# c8t6.net
KiCad netlist of a schematic drawn in Altium Designer
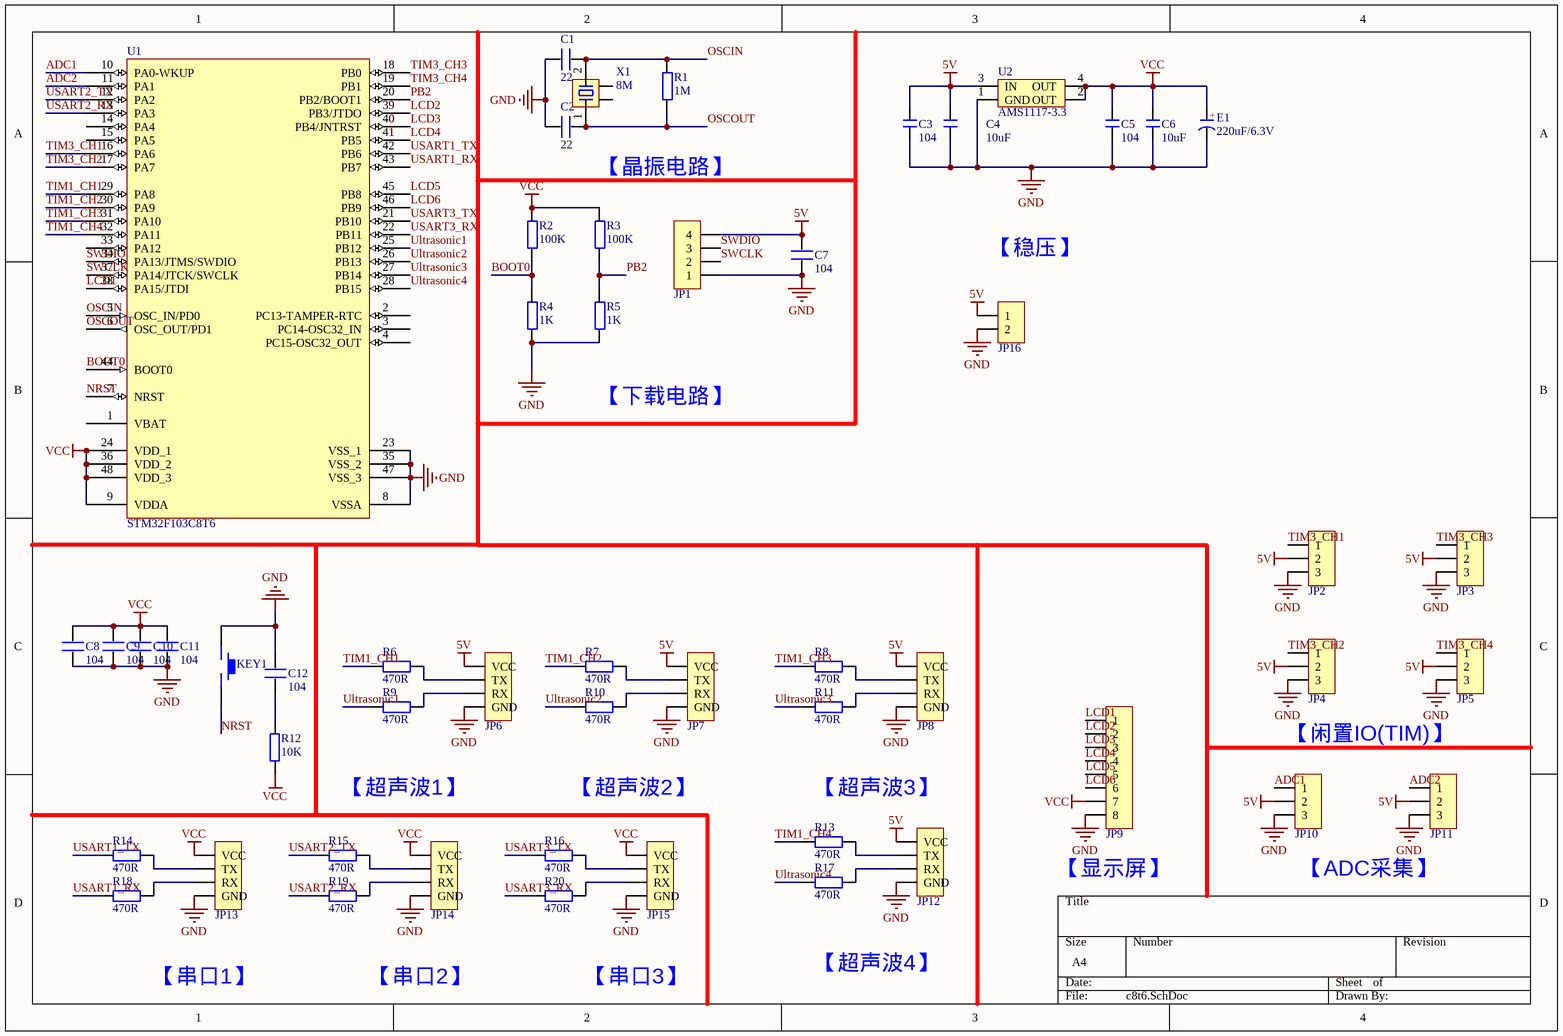
[diagram p0: c8t6.SchDoc]

(export (version "E")
  (design (tool "Eeschema 10.0.6"))
  (components
    (comp (ref "C1") (value "22") (footprint "C 0603") (libsource (lib "CORE") (part "C")))
    (comp (ref "C2") (value "22") (footprint "C 0603") (libsource (lib "CORE") (part "C")))
    (comp (ref "C3")
      (value "104")
      (footprint "C 0603")
      (description "无极性贴片电容")
      (fields (field (name "版权归属") "源创客"))
      (libsource (lib "daplink") (part "C"))
    )
    (comp (ref "C4")
      (value "10uF")
      (footprint "C 0805")
      (description "无极性贴片电容")
      (fields (field (name "版权归属") "源创客"))
      (libsource (lib "daplink") (part "C"))
    )
    (comp (ref "C5")
      (value "104")
      (footprint "C 0603")
      (description "无极性贴片电容")
      (fields (field (name "版权归属") "源创客"))
      (libsource (lib "daplink") (part "C"))
    )
    (comp (ref "C6")
      (value "10uF")
      (footprint "C 0805")
      (description "无极性贴片电容")
      (fields (field (name "版权归属") "源创客"))
      (libsource (lib "daplink") (part "C"))
    )
    (comp (ref "C7") (value "104") (footprint "C 0603") (libsource (lib "CORE") (part "C")))
    (comp (ref "C8") (value "104") (footprint "C 0603") (libsource (lib "CORE") (part "C")))
    (comp (ref "C9") (value "104") (footprint "C 0603") (libsource (lib "CORE") (part "C")))
    (comp (ref "C10") (value "104") (footprint "C 0603") (libsource (lib "CORE") (part "C")))
    (comp (ref "C11") (value "104") (footprint "C 0603") (libsource (lib "CORE") (part "C")))
    (comp (ref "C12") (value "104") (footprint "C 0603") (libsource (lib "CORE") (part "C")))
    (comp (ref "E1")
      (value "220uF/6.3V")
      (footprint "CD C(6032)")
      (description "贴片钽电容")
      (fields (field (name "版权归属") "源创客"))
      (libsource (lib "电阻-电容-电感") (part "C-CD"))
    )
    (comp (ref "JP1")
      (value "HDR-1X4")
      (footprint "XH2.54-4P")
      (description "4P接插件")
      (fields (field (name "版权归属") "源创客"))
      (libsource (lib "") (part "Header 4_1"))
    )
    (comp (ref "JP2")
      (value "HDR-1X3")
      (footprint "HDR-1X3")
      (description "3P接插件")
      (fields (field (name "版权归属") "源创客"))
      (libsource (lib "接插件") (part "Header 3"))
    )
    (comp (ref "JP3")
      (value "HDR-1X3")
      (footprint "HDR-1X3")
      (description "3P接插件")
      (fields (field (name "版权归属") "源创客"))
      (libsource (lib "接插件") (part "Header 3"))
    )
    (comp (ref "JP4")
      (value "HDR-1X3")
      (footprint "HDR-1X3")
      (description "3P接插件")
      (fields (field (name "版权归属") "源创客"))
      (libsource (lib "接插件") (part "Header 3"))
    )
    (comp (ref "JP5")
      (value "HDR-1X3")
      (footprint "HDR-1X3")
      (description "3P接插件")
      (fields (field (name "版权归属") "源创客"))
      (libsource (lib "接插件") (part "Header 3"))
    )
    (comp (ref "JP6")
      (value "HDR-1X4")
      (footprint "XH2.54-4P")
      (description "4P接插件")
      (fields (field (name "版权归属") "源创客"))
      (libsource (lib "接插件") (part "Header 4"))
    )
    (comp (ref "JP7")
      (value "HDR-1X4")
      (footprint "XH2.54-4P")
      (description "4P接插件")
      (fields (field (name "版权归属") "源创客"))
      (libsource (lib "接插件") (part "Header 4"))
    )
    (comp (ref "JP8")
      (value "HDR-1X4")
      (footprint "XH2.54-4P")
      (description "4P接插件")
      (fields (field (name "版权归属") "源创客"))
      (libsource (lib "接插件") (part "Header 4"))
    )
    (comp (ref "JP9")
      (value "HDR-1X8")
      (footprint "HDR-1X8")
      (description "8P接插件")
      (fields (field (name "版权归属") "源创客"))
      (libsource (lib "接插件") (part "Header 8"))
    )
    (comp (ref "JP10")
      (value "HDR-1X3")
      (footprint "HDR-1X3")
      (description "3P接插件")
      (fields (field (name "版权归属") "源创客"))
      (libsource (lib "接插件") (part "Header 3"))
    )
    (comp (ref "JP11")
      (value "HDR-1X3")
      (footprint "HDR-1X3")
      (description "3P接插件")
      (fields (field (name "版权归属") "源创客"))
      (libsource (lib "接插件") (part "Header 3"))
    )
    (comp (ref "JP12")
      (value "HDR-1X4")
      (footprint "XH2.54-4P")
      (description "4P接插件")
      (fields (field (name "版权归属") "源创客"))
      (libsource (lib "接插件") (part "Header 4"))
    )
    (comp (ref "JP13")
      (value "HDR-1X4")
      (footprint "XH2.54-4P")
      (description "4P接插件")
      (fields (field (name "版权归属") "源创客"))
      (libsource (lib "接插件") (part "Header 4"))
    )
    (comp (ref "JP14")
      (value "HDR-1X4")
      (footprint "XH2.54-4P")
      (description "4P接插件")
      (fields (field (name "版权归属") "源创客"))
      (libsource (lib "接插件") (part "Header 4"))
    )
    (comp (ref "JP15")
      (value "HDR-1X4")
      (footprint "XH2.54-4P")
      (description "4P接插件")
      (fields (field (name "版权归属") "源创客"))
      (libsource (lib "接插件") (part "Header 4"))
    )
    (comp (ref "JP16")
      (value "HDR-1X2")
      (footprint "XT60")
      (description "2P接插件")
      (fields (field (name "版权归属") "源创客"))
      (libsource (lib "接插件") (part "Header 2"))
    )
    (comp (ref "KEY1") (value "KEY_M") (footprint "TSW DIP-3*6*4.3") (libsource (lib "CORE") (part "KEY_M")))
    (comp (ref "R1") (value "1M") (footprint "R 0603") (libsource (lib "CORE") (part "R")))
    (comp (ref "R2") (value "100K") (footprint "R 0603") (libsource (lib "CORE") (part "R")))
    (comp (ref "R3") (value "100K") (footprint "R 0603") (libsource (lib "CORE") (part "R")))
    (comp (ref "R4") (value "1K") (footprint "R 0603") (libsource (lib "CORE") (part "R")))
    (comp (ref "R5") (value "1K") (footprint "R 0603") (libsource (lib "CORE") (part "R")))
    (comp (ref "R6")
      (value "470R")
      (footprint "R 0603")
      (description "贴片电阻")
      (fields (field (name "版权归属") "源创客"))
      (libsource (lib "电阻-电容-电感") (part "R"))
    )
    (comp (ref "R7")
      (value "470R")
      (footprint "R 0603")
      (description "贴片电阻")
      (fields (field (name "版权归属") "源创客"))
      (libsource (lib "电阻-电容-电感") (part "R"))
    )
    (comp (ref "R8")
      (value "470R")
      (footprint "R 0603")
      (description "贴片电阻")
      (fields (field (name "版权归属") "源创客"))
      (libsource (lib "电阻-电容-电感") (part "R"))
    )
    (comp (ref "R9")
      (value "470R")
      (footprint "R 0603")
      (description "贴片电阻")
      (fields (field (name "版权归属") "源创客"))
      (libsource (lib "电阻-电容-电感") (part "R"))
    )
    (comp (ref "R10")
      (value "470R")
      (footprint "R 0603")
      (description "贴片电阻")
      (fields (field (name "版权归属") "源创客"))
      (libsource (lib "电阻-电容-电感") (part "R"))
    )
    (comp (ref "R11")
      (value "470R")
      (footprint "R 0603")
      (description "贴片电阻")
      (fields (field (name "版权归属") "源创客"))
      (libsource (lib "电阻-电容-电感") (part "R"))
    )
    (comp (ref "R12") (value "10K") (footprint "R 0603") (libsource (lib "MPU6050") (part "R")))
    (comp (ref "R13")
      (value "470R")
      (footprint "R 0603")
      (description "贴片电阻")
      (fields (field (name "版权归属") "源创客"))
      (libsource (lib "电阻-电容-电感") (part "R"))
    )
    (comp (ref "R14")
      (value "470R")
      (footprint "R 0603")
      (description "贴片电阻")
      (fields (field (name "版权归属") "源创客"))
      (libsource (lib "电阻-电容-电感") (part "R"))
    )
    (comp (ref "R15")
      (value "470R")
      (footprint "R 0603")
      (description "贴片电阻")
      (fields (field (name "版权归属") "源创客"))
      (libsource (lib "电阻-电容-电感") (part "R"))
    )
    (comp (ref "R16")
      (value "470R")
      (footprint "R 0603")
      (description "贴片电阻")
      (fields (field (name "版权归属") "源创客"))
      (libsource (lib "电阻-电容-电感") (part "R"))
    )
    (comp (ref "R17")
      (value "470R")
      (footprint "R 0603")
      (description "贴片电阻")
      (fields (field (name "版权归属") "源创客"))
      (libsource (lib "电阻-电容-电感") (part "R"))
    )
    (comp (ref "R18")
      (value "470R")
      (footprint "R 0603")
      (description "贴片电阻")
      (fields (field (name "版权归属") "源创客"))
      (libsource (lib "电阻-电容-电感") (part "R"))
    )
    (comp (ref "R19")
      (value "470R")
      (footprint "R 0603")
      (description "贴片电阻")
      (fields (field (name "版权归属") "源创客"))
      (libsource (lib "电阻-电容-电感") (part "R"))
    )
    (comp (ref "R20")
      (value "470R")
      (footprint "R 0603")
      (description "贴片电阻")
      (fields (field (name "版权归属") "源创客"))
      (libsource (lib "电阻-电容-电感") (part "R"))
    )
    (comp (ref "U1")
      (value "STM32F103C8T6")
      (footprint "LQFP48 7X7_M")
      (description "Flaah:64/RAM:20/IO:36")
      (fields (field (name "版权归属") "源创客"))
      (libsource (lib "STM32系列单片机") (part "STM32F103C8T6"))
    )
    (comp (ref "U2") (value "AMS1117-3.3") (footprint "SOT223_L") (libsource (lib "GWH") (part "AMS1117")))
    (comp (ref "X1")
      (value "8M")
      (footprint "XTAL-49S DIP")
      (description "4脚晶振")
      (fields (field (name "版权归属") "源创客"))
      (libsource (lib "保险丝-晶振") (part "XTAL-4"))
    )
  )
  (nets
    (net (code "1") (name "/ADC1") (class "Default")
      (node (ref "JP10") (pin "1") (pinfunction "1_1") (pintype "passive"))
      (node (ref "U1") (pin "10") (pinfunction "PA0-WKUP_10") (pintype "bidirectional"))
    )
    (net (code "2") (name "/ADC2") (class "Default")
      (node (ref "JP11") (pin "1") (pinfunction "1_1") (pintype "passive"))
      (node (ref "U1") (pin "11") (pinfunction "PA1_11") (pintype "bidirectional"))
    )
    (net (code "3") (name "/BOOT0") (class "Default")
      (node (ref "R2") (pin "1") (pintype "passive"))
      (node (ref "R4") (pin "2") (pintype "passive"))
      (node (ref "U1") (pin "44") (pinfunction "BOOT0_44") (pintype "input"))
    )
    (net (code "4") (name "/LCD1") (class "Default")
      (node (ref "JP9") (pin "1") (pinfunction "1_1") (pintype "passive"))
      (node (ref "U1") (pin "38") (pinfunction "PA15/JTDI_38") (pintype "bidirectional"))
    )
    (net (code "5") (name "/LCD2") (class "Default")
      (node (ref "JP9") (pin "2") (pinfunction "2_2") (pintype "passive"))
      (node (ref "U1") (pin "39") (pinfunction "PB3/JTDO_39") (pintype "bidirectional"))
    )
    (net (code "6") (name "/LCD3") (class "Default")
      (node (ref "JP9") (pin "3") (pinfunction "3_3") (pintype "passive"))
      (node (ref "U1") (pin "40") (pinfunction "PB4/JNTRST_40") (pintype "bidirectional"))
    )
    (net (code "7") (name "/LCD4") (class "Default")
      (node (ref "JP9") (pin "4") (pinfunction "4_4") (pintype "passive"))
      (node (ref "U1") (pin "41") (pinfunction "PB5_41") (pintype "bidirectional"))
    )
    (net (code "8") (name "/LCD5") (class "Default")
      (node (ref "JP9") (pin "5") (pinfunction "5_5") (pintype "passive"))
      (node (ref "U1") (pin "45") (pinfunction "PB8_45") (pintype "bidirectional"))
    )
    (net (code "9") (name "/LCD6") (class "Default")
      (node (ref "JP9") (pin "6") (pinfunction "6_6") (pintype "passive"))
      (node (ref "U1") (pin "46") (pinfunction "PB9_46") (pintype "bidirectional"))
    )
    (net (code "10") (name "/NRST") (class "Default")
      (node (ref "KEY1") (pin "2") (pinfunction "2_2") (pintype "passive"))
      (node (ref "U1") (pin "7") (pinfunction "NRST_7") (pintype "bidirectional"))
    )
    (net (code "11") (name "/OSCIN") (class "Default")
      (node (ref "C1") (pin "1") (pintype "passive"))
      (node (ref "R1") (pin "2") (pintype "passive"))
      (node (ref "U1") (pin "5") (pinfunction "OSC_IN/PD0_5") (pintype "input"))
      (node (ref "X1") (pin "2") (pinfunction "3_2") (pintype "passive"))
    )
    (net (code "12") (name "/OSCOUT") (class "Default")
      (node (ref "C2") (pin "1") (pintype "passive"))
      (node (ref "R1") (pin "1") (pintype "passive"))
      (node (ref "U1") (pin "6") (pinfunction "OSC_OUT/PD1_6") (pintype "output"))
      (node (ref "X1") (pin "1") (pinfunction "1_1") (pintype "passive"))
    )
    (net (code "13") (name "/PB2") (class "Default")
      (node (ref "R3") (pin "1") (pintype "passive"))
      (node (ref "R5") (pin "2") (pintype "passive"))
      (node (ref "U1") (pin "20") (pinfunction "PB2/BOOT1_20") (pintype "bidirectional"))
    )
    (net (code "14") (name "/SWCLK") (class "Default")
      (node (ref "JP1") (pin "2") (pinfunction "2_2") (pintype "passive"))
      (node (ref "U1") (pin "37") (pinfunction "PA14/JTCK/SWCLK_37") (pintype "bidirectional"))
    )
    (net (code "15") (name "/SWDIO") (class "Default")
      (node (ref "JP1") (pin "3") (pinfunction "3_3") (pintype "passive"))
      (node (ref "U1") (pin "34") (pinfunction "PA13/JTMS/SWDIO_34") (pintype "bidirectional"))
    )
    (net (code "16") (name "/TIM1_CH1") (class "Default")
      (node (ref "R6") (pin "1") (pinfunction "1_1") (pintype "passive"))
      (node (ref "U1") (pin "29") (pinfunction "PA8_29") (pintype "bidirectional"))
    )
    (net (code "17") (name "/TIM1_CH2") (class "Default")
      (node (ref "R7") (pin "1") (pinfunction "1_1") (pintype "passive"))
      (node (ref "U1") (pin "30") (pinfunction "PA9_30") (pintype "bidirectional"))
    )
    (net (code "18") (name "/TIM1_CH3") (class "Default")
      (node (ref "R8") (pin "1") (pinfunction "1_1") (pintype "passive"))
      (node (ref "U1") (pin "31") (pinfunction "PA10_31") (pintype "bidirectional"))
    )
    (net (code "19") (name "/TIM1_CH4") (class "Default")
      (node (ref "R13") (pin "1") (pinfunction "1_1") (pintype "passive"))
      (node (ref "U1") (pin "32") (pinfunction "PA11_32") (pintype "bidirectional"))
    )
    (net (code "20") (name "/TIM3_CH1") (class "Default")
      (node (ref "JP2") (pin "1") (pinfunction "1_1") (pintype "passive"))
      (node (ref "U1") (pin "16") (pinfunction "PA6_16") (pintype "bidirectional"))
    )
    (net (code "21") (name "/TIM3_CH2") (class "Default")
      (node (ref "JP4") (pin "1") (pinfunction "1_1") (pintype "passive"))
      (node (ref "U1") (pin "17") (pinfunction "PA7_17") (pintype "bidirectional"))
    )
    (net (code "22") (name "/TIM3_CH3") (class "Default")
      (node (ref "JP3") (pin "1") (pinfunction "1_1") (pintype "passive"))
      (node (ref "U1") (pin "18") (pinfunction "PB0_18") (pintype "bidirectional"))
    )
    (net (code "23") (name "/TIM3_CH4") (class "Default")
      (node (ref "JP5") (pin "1") (pinfunction "1_1") (pintype "passive"))
      (node (ref "U1") (pin "19") (pinfunction "PB1_19") (pintype "bidirectional"))
    )
    (net (code "24") (name "/USART1_RX") (class "Default")
      (node (ref "R18") (pin "1") (pinfunction "1_1") (pintype "passive"))
      (node (ref "U1") (pin "43") (pinfunction "PB7_43") (pintype "bidirectional"))
    )
    (net (code "25") (name "/USART1_TX") (class "Default")
      (node (ref "R14") (pin "1") (pinfunction "1_1") (pintype "passive"))
      (node (ref "U1") (pin "42") (pinfunction "PB6_42") (pintype "bidirectional"))
    )
    (net (code "26") (name "/USART2_RX") (class "Default")
      (node (ref "R19") (pin "1") (pinfunction "1_1") (pintype "passive"))
      (node (ref "U1") (pin "13") (pinfunction "PA3_13") (pintype "bidirectional"))
    )
    (net (code "27") (name "/USART2_TX") (class "Default")
      (node (ref "R15") (pin "1") (pinfunction "1_1") (pintype "passive"))
      (node (ref "U1") (pin "12") (pinfunction "PA2_12") (pintype "bidirectional"))
    )
    (net (code "28") (name "/USART3_RX") (class "Default")
      (node (ref "R20") (pin "1") (pinfunction "1_1") (pintype "passive"))
      (node (ref "U1") (pin "22") (pinfunction "PB11_22") (pintype "bidirectional"))
    )
    (net (code "29") (name "/USART3_TX") (class "Default")
      (node (ref "R16") (pin "1") (pinfunction "1_1") (pintype "passive"))
      (node (ref "U1") (pin "21") (pinfunction "PB10_21") (pintype "bidirectional"))
    )
    (net (code "30") (name "/Ultrasonic1") (class "Default")
      (node (ref "R9") (pin "1") (pinfunction "1_1") (pintype "passive"))
      (node (ref "U1") (pin "25") (pinfunction "PB12_25") (pintype "bidirectional"))
    )
    (net (code "31") (name "/Ultrasonic2") (class "Default")
      (node (ref "R10") (pin "1") (pinfunction "1_1") (pintype "passive"))
      (node (ref "U1") (pin "26") (pinfunction "PB13_26") (pintype "bidirectional"))
    )
    (net (code "32") (name "/Ultrasonic3") (class "Default")
      (node (ref "R11") (pin "1") (pinfunction "1_1") (pintype "passive"))
      (node (ref "U1") (pin "27") (pinfunction "PB14_27") (pintype "bidirectional"))
    )
    (net (code "33") (name "/Ultrasonic4") (class "Default")
      (node (ref "R17") (pin "1") (pinfunction "1_1") (pintype "passive"))
      (node (ref "U1") (pin "28") (pinfunction "PB15_28") (pintype "bidirectional"))
    )
    (net (code "34") (name "5V") (class "Default")
      (node (ref "C3") (pin "2") (pinfunction "2_2") (pintype "passive"))
      (node (ref "C4") (pin "2") (pinfunction "2_2") (pintype "passive"))
      (node (ref "C7") (pin "1") (pintype "passive"))
      (node (ref "JP1") (pin "4") (pinfunction "4_4") (pintype "passive"))
      (node (ref "JP10") (pin "2") (pinfunction "2_2") (pintype "passive"))
      (node (ref "JP11") (pin "2") (pinfunction "2_2") (pintype "passive"))
      (node (ref "JP12") (pin "1") (pinfunction "VCC_1") (pintype "passive"))
      (node (ref "JP16") (pin "1") (pinfunction "1_1") (pintype "passive"))
      (node (ref "JP2") (pin "2") (pinfunction "2_2") (pintype "passive"))
      (node (ref "JP3") (pin "2") (pinfunction "2_2") (pintype "passive"))
      (node (ref "JP4") (pin "2") (pinfunction "2_2") (pintype "passive"))
      (node (ref "JP5") (pin "2") (pinfunction "2_2") (pintype "passive"))
      (node (ref "JP6") (pin "1") (pinfunction "VCC_1") (pintype "passive"))
      (node (ref "JP7") (pin "1") (pinfunction "VCC_1") (pintype "passive"))
      (node (ref "JP8") (pin "1") (pinfunction "VCC_1") (pintype "passive"))
      (node (ref "U2") (pin "3") (pinfunction "IN_3") (pintype "passive"))
    )
    (net (code "35") (name "GND") (class "Default")
      (node (ref "C1") (pin "2") (pintype "passive"))
      (node (ref "C10") (pin "2") (pintype "passive"))
      (node (ref "C11") (pin "2") (pintype "passive"))
      (node (ref "C12") (pin "2") (pintype "passive"))
      (node (ref "C2") (pin "2") (pintype "passive"))
      (node (ref "C3") (pin "1") (pinfunction "1_1") (pintype "passive"))
      (node (ref "C4") (pin "1") (pinfunction "1_1") (pintype "passive"))
      (node (ref "C5") (pin "1") (pinfunction "1_1") (pintype "passive"))
      (node (ref "C6") (pin "1") (pinfunction "1_1") (pintype "passive"))
      (node (ref "C7") (pin "2") (pintype "passive"))
      (node (ref "C8") (pin "2") (pintype "passive"))
      (node (ref "C9") (pin "2") (pintype "passive"))
      (node (ref "E1") (pin "2") (pinfunction "K_2") (pintype "passive"))
      (node (ref "JP1") (pin "1") (pinfunction "1_1") (pintype "passive"))
      (node (ref "JP10") (pin "3") (pinfunction "3_3") (pintype "passive"))
      (node (ref "JP11") (pin "3") (pinfunction "3_3") (pintype "passive"))
      (node (ref "JP12") (pin "4") (pinfunction "GND_4") (pintype "passive"))
      (node (ref "JP13") (pin "4") (pinfunction "GND_4") (pintype "passive"))
      (node (ref "JP14") (pin "4") (pinfunction "GND_4") (pintype "passive"))
      (node (ref "JP15") (pin "4") (pinfunction "GND_4") (pintype "passive"))
      (node (ref "JP16") (pin "2") (pinfunction "2_2") (pintype "passive"))
      (node (ref "JP2") (pin "3") (pinfunction "3_3") (pintype "passive"))
      (node (ref "JP3") (pin "3") (pinfunction "3_3") (pintype "passive"))
      (node (ref "JP4") (pin "3") (pinfunction "3_3") (pintype "passive"))
      (node (ref "JP5") (pin "3") (pinfunction "3_3") (pintype "passive"))
      (node (ref "JP6") (pin "4") (pinfunction "GND_4") (pintype "passive"))
      (node (ref "JP7") (pin "4") (pinfunction "GND_4") (pintype "passive"))
      (node (ref "JP8") (pin "4") (pinfunction "GND_4") (pintype "passive"))
      (node (ref "JP9") (pin "8") (pinfunction "8_8") (pintype "passive"))
      (node (ref "KEY1") (pin "1") (pinfunction "1_1") (pintype "passive"))
      (node (ref "R4") (pin "1") (pintype "passive"))
      (node (ref "R5") (pin "1") (pintype "passive"))
      (node (ref "U1") (pin "23") (pinfunction "VSS_1_23") (pintype "power_in"))
      (node (ref "U1") (pin "35") (pinfunction "VSS_2_35") (pintype "power_in"))
      (node (ref "U1") (pin "47") (pinfunction "VSS_3_47") (pintype "power_in"))
      (node (ref "U1") (pin "8") (pinfunction "VSSA_8") (pintype "power_in"))
      (node (ref "U2") (pin "1") (pinfunction "GND_1") (pintype "passive"))
    )
    (net (code "36") (name "Net-(C12-Pad1)") (class "Default")
      (node (ref "C12") (pin "1") (pintype "passive"))
      (node (ref "R12") (pin "1") (pintype "passive"))
    )
    (net (code "37") (name "Net-(JP6-RX)") (class "Default")
      (node (ref "JP6") (pin "3") (pinfunction "RX_3") (pintype "passive"))
      (node (ref "R9") (pin "2") (pinfunction "2_2") (pintype "passive"))
    )
    (net (code "38") (name "Net-(JP6-TX)") (class "Default")
      (node (ref "JP6") (pin "2") (pinfunction "TX_2") (pintype "passive"))
      (node (ref "R6") (pin "2") (pinfunction "2_2") (pintype "passive"))
    )
    (net (code "39") (name "Net-(JP7-RX)") (class "Default")
      (node (ref "JP7") (pin "3") (pinfunction "RX_3") (pintype "passive"))
      (node (ref "R10") (pin "2") (pinfunction "2_2") (pintype "passive"))
    )
    (net (code "40") (name "Net-(JP7-TX)") (class "Default")
      (node (ref "JP7") (pin "2") (pinfunction "TX_2") (pintype "passive"))
      (node (ref "R7") (pin "2") (pinfunction "2_2") (pintype "passive"))
    )
    (net (code "41") (name "Net-(JP8-RX)") (class "Default")
      (node (ref "JP8") (pin "3") (pinfunction "RX_3") (pintype "passive"))
      (node (ref "R11") (pin "2") (pinfunction "2_2") (pintype "passive"))
    )
    (net (code "42") (name "Net-(JP8-TX)") (class "Default")
      (node (ref "JP8") (pin "2") (pinfunction "TX_2") (pintype "passive"))
      (node (ref "R8") (pin "2") (pinfunction "2_2") (pintype "passive"))
    )
    (net (code "43") (name "Net-(JP12-RX)") (class "Default")
      (node (ref "JP12") (pin "3") (pinfunction "RX_3") (pintype "passive"))
      (node (ref "R17") (pin "2") (pinfunction "2_2") (pintype "passive"))
    )
    (net (code "44") (name "Net-(JP12-TX)") (class "Default")
      (node (ref "JP12") (pin "2") (pinfunction "TX_2") (pintype "passive"))
      (node (ref "R13") (pin "2") (pinfunction "2_2") (pintype "passive"))
    )
    (net (code "45") (name "Net-(JP13-RX)") (class "Default")
      (node (ref "JP13") (pin "3") (pinfunction "RX_3") (pintype "passive"))
      (node (ref "R18") (pin "2") (pinfunction "2_2") (pintype "passive"))
    )
    (net (code "46") (name "Net-(JP13-TX)") (class "Default")
      (node (ref "JP13") (pin "2") (pinfunction "TX_2") (pintype "passive"))
      (node (ref "R14") (pin "2") (pinfunction "2_2") (pintype "passive"))
    )
    (net (code "47") (name "Net-(JP14-RX)") (class "Default")
      (node (ref "JP14") (pin "3") (pinfunction "RX_3") (pintype "passive"))
      (node (ref "R19") (pin "2") (pinfunction "2_2") (pintype "passive"))
    )
    (net (code "48") (name "Net-(JP14-TX)") (class "Default")
      (node (ref "JP14") (pin "2") (pinfunction "TX_2") (pintype "passive"))
      (node (ref "R15") (pin "2") (pinfunction "2_2") (pintype "passive"))
    )
    (net (code "49") (name "Net-(JP15-RX)") (class "Default")
      (node (ref "JP15") (pin "3") (pinfunction "RX_3") (pintype "passive"))
      (node (ref "R20") (pin "2") (pinfunction "2_2") (pintype "passive"))
    )
    (net (code "50") (name "Net-(JP15-TX)") (class "Default")
      (node (ref "JP15") (pin "2") (pinfunction "TX_2") (pintype "passive"))
      (node (ref "R16") (pin "2") (pinfunction "2_2") (pintype "passive"))
    )
    (net (code "51") (name "VCC") (class "Default")
      (node (ref "C10") (pin "1") (pintype "passive"))
      (node (ref "C11") (pin "1") (pintype "passive"))
      (node (ref "C5") (pin "2") (pinfunction "2_2") (pintype "passive"))
      (node (ref "C6") (pin "2") (pinfunction "2_2") (pintype "passive"))
      (node (ref "C8") (pin "1") (pintype "passive"))
      (node (ref "C9") (pin "1") (pintype "passive"))
      (node (ref "E1") (pin "1") (pinfunction "A_1") (pintype "passive"))
      (node (ref "JP13") (pin "1") (pinfunction "VCC_1") (pintype "passive"))
      (node (ref "JP14") (pin "1") (pinfunction "VCC_1") (pintype "passive"))
      (node (ref "JP15") (pin "1") (pinfunction "VCC_1") (pintype "passive"))
      (node (ref "JP9") (pin "7") (pinfunction "7_7") (pintype "passive"))
      (node (ref "R12") (pin "2") (pintype "passive"))
      (node (ref "R2") (pin "2") (pintype "passive"))
      (node (ref "R3") (pin "2") (pintype "passive"))
      (node (ref "U1") (pin "24") (pinfunction "VDD_1_24") (pintype "power_in"))
      (node (ref "U1") (pin "36") (pinfunction "VDD_2_36") (pintype "power_in"))
      (node (ref "U1") (pin "48") (pinfunction "VDD_3_48") (pintype "power_in"))
      (node (ref "U1") (pin "9") (pinfunction "VDDA_9") (pintype "power_in"))
      (node (ref "U2") (pin "2") (pinfunction "OUT_2") (pintype "passive"))
      (node (ref "U2") (pin "4") (pinfunction "OUT_4") (pintype "passive"))
    )
    (net (code "52") (name "unconnected-(U1-PA4-Pad14)") (class "Default")
      (node (ref "U1") (pin "14") (pinfunction "PA4_14") (pintype "bidirectional"))
    )
    (net (code "53") (name "unconnected-(U1-PA5-Pad15)") (class "Default")
      (node (ref "U1") (pin "15") (pinfunction "PA5_15") (pintype "bidirectional"))
    )
    (net (code "54") (name "unconnected-(U1-PA12-Pad33)") (class "Default")
      (node (ref "U1") (pin "33") (pinfunction "PA12_33") (pintype "bidirectional"))
    )
    (net (code "55") (name "unconnected-(U1-PC13-TAMPER-RTC-Pad2)") (class "Default")
      (node (ref "U1") (pin "2") (pinfunction "PC13-TAMPER-RTC_2") (pintype "bidirectional"))
    )
    (net (code "56") (name "unconnected-(U1-PC14-OSC32_IN-Pad3)") (class "Default")
      (node (ref "U1") (pin "3") (pinfunction "PC14-OSC32_IN_3") (pintype "bidirectional"))
    )
    (net (code "57") (name "unconnected-(U1-PC15-OSC32_OUT-Pad4)") (class "Default")
      (node (ref "U1") (pin "4") (pinfunction "PC15-OSC32_OUT_4") (pintype "bidirectional"))
    )
    (net (code "58") (name "unconnected-(U1-VBAT-Pad1)") (class "Default")
      (node (ref "U1") (pin "1") (pinfunction "VBAT_1") (pintype "power_in"))
    )
    (net (code "59") (name "unconnected-(X1-2-Pad3)") (class "Default")
      (node (ref "X1") (pin "3") (pinfunction "2_3") (pintype "passive"))
    )
    (net (code "60") (name "unconnected-(X1-Pad4)") (class "Default")
      (node (ref "X1") (pin "4") (pinfunction "4_4") (pintype "passive"))
    )
  )
)
